# RGBBlinkyCR2032.net
KiCad netlist of a schematic drawn in EAGLE
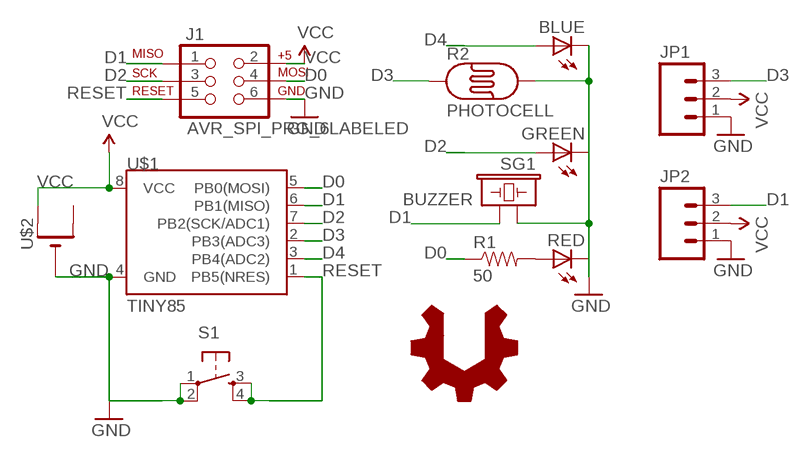
[diagram p0: schematic, sheet 1]

(export (version "E")
  (design (tool "Eeschema 10.0.6"))
  (components
    (comp (ref "BLUE")
      (value "LED5MM")
      (footprint "eagle-import:LED5MM")
      (libsource (lib "eagle-import") (part "LED5MM"))
    )
    (comp (ref "GREEN")
      (value "LED5MM")
      (footprint "eagle-import:LED5MM")
      (libsource (lib "eagle-import") (part "LED5MM"))
    )
    (comp (ref "J1")
      (value "AVR_SPI_PRG_6LABELED")
      (footprint "eagle-import:2X3-NS")
      (libsource (lib "eagle-import") (part "AVR_SPI_PRG_6LABELED"))
    )
    (comp (ref "JP1")
      (value "M03PTH")
      (footprint "eagle-import:1X03")
      (libsource (lib "eagle-import") (part "M03PTH"))
    )
    (comp (ref "JP2")
      (value "M03PTH")
      (footprint "eagle-import:1X03")
      (libsource (lib "eagle-import") (part "M03PTH"))
    )
    (comp (ref "R1")
      (value "50")
      (footprint "eagle-import:AXIAL-0.3")
      (libsource (lib "eagle-import") (part "RESISTORAXIAL-0.3"))
    )
    (comp (ref "R2")
      (value "PHOTOCELL")
      (footprint "eagle-import:PHOTOCELL")
      (libsource (lib "eagle-import") (part "PHOTOCELLPTH"))
    )
    (comp (ref "RED")
      (value "LED5MM")
      (footprint "eagle-import:LED5MM")
      (libsource (lib "eagle-import") (part "LED5MM"))
    )
    (comp (ref "S1")
      (value "TAC_SWITCHPTH")
      (footprint "eagle-import:TACTILE-PTH")
      (libsource (lib "eagle-import") (part "TAC_SWITCHPTH"))
    )
    (comp (ref "SG1")
      (value "BUZZER")
      (footprint "eagle-import:BUZZER-12MM")
      (libsource (lib "eagle-import") (part "BUZZERPTH"))
    )
    (comp (ref "U$1")
      (value "TINY85")
      (footprint "eagle-import:DIP08")
      (libsource (lib "eagle-import") (part "ATTINY13DIP"))
    )
    (comp (ref "U$2")
      (value "CR2032THM")
      (footprint "eagle-import:CR2032-THRU")
      (libsource (lib "eagle-import") (part "CR2032THM"))
    )
    (comp (ref "U$3")
      (value "USER_HACKABLE")
      (footprint "eagle-import:USER_HACKABLE")
      (libsource (lib "eagle-import") (part "USER_HACKABLE"))
    )
  )
  (nets
    (net (code "1") (name "/D0") (class "Default")
      (node (ref "J1") (pin "4") (pinfunction "MOSI_4") (pintype "passive"))
      (node (ref "R1") (pin "P$1") (pinfunction "1_P$1") (pintype "passive"))
      (node (ref "U$1") (pin "5") (pinfunction "PB0(MOSI)_5") (pintype "bidirectional"))
    )
    (net (code "2") (name "/D1") (class "Default")
      (node (ref "J1") (pin "1") (pinfunction "MISO_1") (pintype "passive"))
      (node (ref "JP2") (pin "3") (pinfunction "3_3") (pintype "passive"))
      (node (ref "SG1") (pin "-") (pinfunction "2_-") (pintype "passive"))
      (node (ref "U$1") (pin "6") (pinfunction "PB1(MISO)_6") (pintype "bidirectional"))
    )
    (net (code "3") (name "/D2") (class "Default")
      (node (ref "GREEN") (pin "A") (pinfunction "A_A") (pintype "passive"))
      (node (ref "J1") (pin "3") (pinfunction "SCK_3") (pintype "passive"))
      (node (ref "U$1") (pin "7") (pinfunction "PB2(SCK/ADC1)_7") (pintype "bidirectional"))
    )
    (net (code "4") (name "/D3") (class "Default")
      (node (ref "JP1") (pin "3") (pinfunction "3_3") (pintype "passive"))
      (node (ref "R2") (pin "1") (pinfunction "P$1_1") (pintype "bidirectional"))
      (node (ref "U$1") (pin "2") (pinfunction "PB3(ADC3)_2") (pintype "bidirectional"))
    )
    (net (code "5") (name "/D4") (class "Default")
      (node (ref "BLUE") (pin "A") (pinfunction "A_A") (pintype "passive"))
      (node (ref "U$1") (pin "3") (pinfunction "PB4(ADC2)_3") (pintype "bidirectional"))
    )
    (net (code "6") (name "/RESET") (class "Default")
      (node (ref "J1") (pin "5") (pinfunction "RST_5") (pintype "passive"))
      (node (ref "S1") (pin "3") (pinfunction "3_3") (pintype "passive"))
      (node (ref "S1") (pin "4") (pinfunction "4_4") (pintype "passive"))
      (node (ref "U$1") (pin "1") (pinfunction "PB5(NRES)_1") (pintype "bidirectional"))
    )
    (net (code "7") (name "GND") (class "Default")
      (node (ref "BLUE") (pin "K") (pinfunction "C_K") (pintype "passive"))
      (node (ref "GREEN") (pin "K") (pinfunction "C_K") (pintype "passive"))
      (node (ref "J1") (pin "6") (pinfunction "GND_6") (pintype "passive"))
      (node (ref "JP1") (pin "1") (pinfunction "1_1") (pintype "passive"))
      (node (ref "JP2") (pin "1") (pinfunction "1_1") (pintype "passive"))
      (node (ref "R2") (pin "2") (pinfunction "P$2_2") (pintype "bidirectional"))
      (node (ref "RED") (pin "K") (pinfunction "C_K") (pintype "passive"))
      (node (ref "S1") (pin "1") (pinfunction "1_1") (pintype "passive"))
      (node (ref "S1") (pin "2") (pinfunction "2_2") (pintype "passive"))
      (node (ref "SG1") (pin "+") (pinfunction "1_+") (pintype "passive"))
      (node (ref "U$1") (pin "4") (pinfunction "GND_4") (pintype "bidirectional"))
      (node (ref "U$2") (pin "-") (pinfunction "-_-") (pintype "passive"))
    )
    (net (code "8") (name "Net-(R1-2)") (class "Default")
      (node (ref "R1") (pin "P$2") (pinfunction "2_P$2") (pintype "passive"))
      (node (ref "RED") (pin "A") (pinfunction "A_A") (pintype "passive"))
    )
    (net (code "9") (name "VCC") (class "Default")
      (node (ref "J1") (pin "2") (pinfunction "V+_2") (pintype "passive"))
      (node (ref "JP1") (pin "2") (pinfunction "2_2") (pintype "passive"))
      (node (ref "JP2") (pin "2") (pinfunction "2_2") (pintype "passive"))
      (node (ref "U$1") (pin "8") (pinfunction "VCC_8") (pintype "bidirectional"))
      (node (ref "U$2") (pin "+1") (pinfunction "+_+1") (pintype "passive"))
    )
    (net (code "10") (name "unconnected-(U$2-+1-Pad+2)") (class "Default")
      (node (ref "U$2") (pin "+2") (pinfunction "+1_+2") (pintype "passive"))
    )
  )
)
